# Adafruit_HTU21DF_Breakout.net
KiCad netlist of a schematic drawn in EAGLE
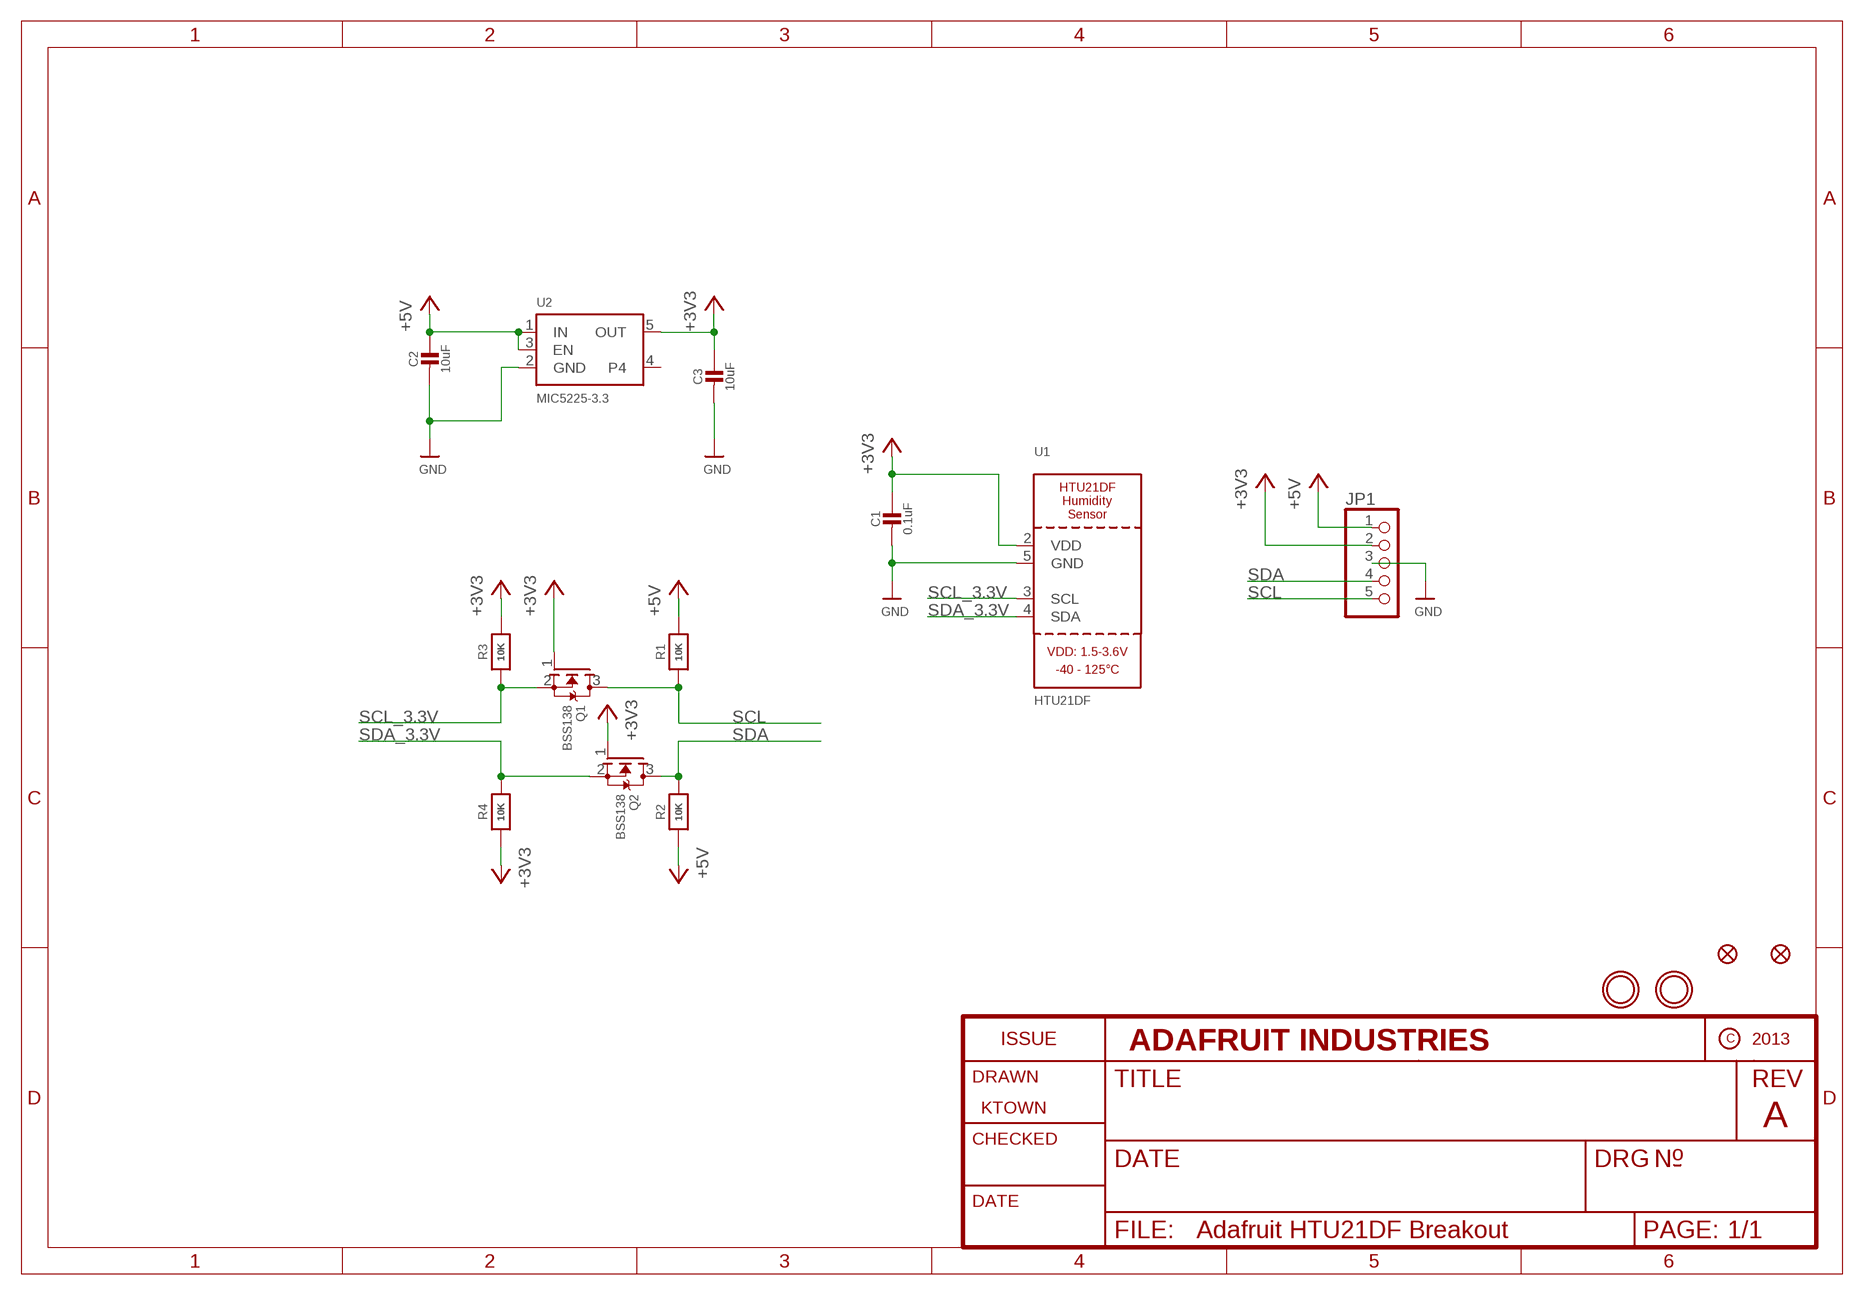
[diagram p0: schematic, sheet 1]

(export (version "E")
  (design (tool "Eeschema 10.0.6"))
  (components
    (comp (ref "C1")
      (value "0.1uF")
      (footprint "eagle-import:0805-NO")
      (libsource (lib "eagle-import") (part "CAP_CERAMIC0805-NOOUTLINE"))
    )
    (comp (ref "C2")
      (value "10uF")
      (footprint "eagle-import:0805-NO")
      (libsource (lib "eagle-import") (part "CAP_CERAMIC0805-NOOUTLINE"))
    )
    (comp (ref "C3")
      (value "10uF")
      (footprint "eagle-import:0805-NO")
      (libsource (lib "eagle-import") (part "CAP_CERAMIC0805-NOOUTLINE"))
    )
    (comp (ref "FID1")
      (value "FIDUCIAL\"\"")
      (footprint "eagle-import:FIDUCIAL_1MM")
      (libsource (lib "eagle-import") (part "FIDUCIAL{dblquote}{dblquote}"))
    )
    (comp (ref "FID2")
      (value "FIDUCIAL\"\"")
      (footprint "eagle-import:FIDUCIAL_1MM")
      (libsource (lib "eagle-import") (part "FIDUCIAL{dblquote}{dblquote}"))
    )
    (comp (ref "JP1")
      (value "HEADER-1X570MIL")
      (footprint "eagle-import:1X05_ROUND_70")
      (libsource (lib "eagle-import") (part "HEADER-1X570MIL"))
    )
    (comp (ref "Q1")
      (value "BSS138")
      (footprint "eagle-import:SOT23-WIDE")
      (libsource (lib "eagle-import") (part "MOSFET-NWIDE"))
    )
    (comp (ref "Q2")
      (value "BSS138")
      (footprint "eagle-import:SOT23-WIDE")
      (libsource (lib "eagle-import") (part "MOSFET-NWIDE"))
    )
    (comp (ref "R1")
      (value "10K")
      (footprint "eagle-import:0805-NO")
      (libsource (lib "eagle-import") (part "RESISTOR0805_NOOUTLINE"))
    )
    (comp (ref "R2")
      (value "10K")
      (footprint "eagle-import:0805-NO")
      (libsource (lib "eagle-import") (part "RESISTOR0805_NOOUTLINE"))
    )
    (comp (ref "R3")
      (value "10K")
      (footprint "eagle-import:0805-NO")
      (libsource (lib "eagle-import") (part "RESISTOR0805_NOOUTLINE"))
    )
    (comp (ref "R4")
      (value "10K")
      (footprint "eagle-import:0805-NO")
      (libsource (lib "eagle-import") (part "RESISTOR0805_NOOUTLINE"))
    )
    (comp (ref "U$3")
      (value "MOUNTINGHOLE2.5")
      (footprint "eagle-import:MOUNTINGHOLE_2.5_PLATED")
      (libsource (lib "eagle-import") (part "MOUNTINGHOLE2.5"))
    )
    (comp (ref "U$4")
      (value "MOUNTINGHOLE2.5")
      (footprint "eagle-import:MOUNTINGHOLE_2.5_PLATED")
      (libsource (lib "eagle-import") (part "MOUNTINGHOLE2.5"))
    )
    (comp (ref "U1")
      (value "HTU21DF")
      (footprint "eagle-import:HTU21DF")
      (libsource (lib "eagle-import") (part "HTU21DF"))
    )
    (comp (ref "U2")
      (value "MIC5225-3.3")
      (footprint "eagle-import:SOT23-5")
      (libsource (lib "eagle-import") (part "VREG_SOT23-5"))
    )
  )
  (nets
    (net (code "1") (name "+3V3") (class "Default")
      (node (ref "C1") (pin "1") (pinfunction "1_1") (pintype "passive"))
      (node (ref "C3") (pin "1") (pinfunction "1_1") (pintype "passive"))
      (node (ref "JP1") (pin "2") (pinfunction "2_2") (pintype "passive"))
      (node (ref "Q1") (pin "1") (pinfunction "G_1") (pintype "bidirectional"))
      (node (ref "Q2") (pin "1") (pinfunction "G_1") (pintype "bidirectional"))
      (node (ref "R3") (pin "2") (pinfunction "2_2") (pintype "passive"))
      (node (ref "R4") (pin "1") (pinfunction "1_1") (pintype "passive"))
      (node (ref "U1") (pin "2") (pinfunction "VDD_2") (pintype "power_in"))
      (node (ref "U2") (pin "5") (pinfunction "OUT_5") (pintype "power_in"))
    )
    (net (code "2") (name "+5V") (class "Default")
      (node (ref "C2") (pin "1") (pinfunction "1_1") (pintype "passive"))
      (node (ref "JP1") (pin "1") (pinfunction "1_1") (pintype "passive"))
      (node (ref "R1") (pin "2") (pinfunction "2_2") (pintype "passive"))
      (node (ref "R2") (pin "1") (pinfunction "1_1") (pintype "passive"))
      (node (ref "U2") (pin "1") (pinfunction "IN_1") (pintype "power_in"))
      (node (ref "U2") (pin "3") (pinfunction "EN_3") (pintype "input"))
    )
    (net (code "3") (name "/SCL") (class "Default")
      (node (ref "JP1") (pin "5") (pinfunction "5_5") (pintype "passive"))
      (node (ref "Q1") (pin "3") (pinfunction "D_3") (pintype "bidirectional"))
      (node (ref "R1") (pin "1") (pinfunction "1_1") (pintype "passive"))
    )
    (net (code "4") (name "/SCL_3.3V") (class "Default")
      (node (ref "Q1") (pin "2") (pinfunction "S_2") (pintype "bidirectional"))
      (node (ref "R3") (pin "1") (pinfunction "1_1") (pintype "passive"))
      (node (ref "U1") (pin "3") (pinfunction "SCL_3") (pintype "input"))
    )
    (net (code "5") (name "/SDA") (class "Default")
      (node (ref "JP1") (pin "4") (pinfunction "4_4") (pintype "passive"))
      (node (ref "Q2") (pin "3") (pinfunction "D_3") (pintype "bidirectional"))
      (node (ref "R2") (pin "2") (pinfunction "2_2") (pintype "passive"))
    )
    (net (code "6") (name "/SDA_3.3V") (class "Default")
      (node (ref "Q2") (pin "2") (pinfunction "S_2") (pintype "bidirectional"))
      (node (ref "R4") (pin "2") (pinfunction "2_2") (pintype "passive"))
      (node (ref "U1") (pin "4") (pinfunction "SDA_4") (pintype "bidirectional"))
    )
    (net (code "7") (name "GND") (class "Default")
      (node (ref "C1") (pin "2") (pinfunction "2_2") (pintype "passive"))
      (node (ref "C2") (pin "2") (pinfunction "2_2") (pintype "passive"))
      (node (ref "C3") (pin "2") (pinfunction "2_2") (pintype "passive"))
      (node (ref "JP1") (pin "3") (pinfunction "3_3") (pintype "passive"))
      (node (ref "U1") (pin "5") (pinfunction "GND_5") (pintype "power_in"))
      (node (ref "U2") (pin "2") (pinfunction "GND_2") (pintype "power_in"))
    )
    (net (code "8") (name "unconnected-(U2-P4-Pad4)") (class "Default")
      (node (ref "U2") (pin "4") (pinfunction "P4_4") (pintype "bidirectional"))
    )
  )
)
